# Stromsenke_Board.net
KiCad netlist of a schematic drawn in EAGLE
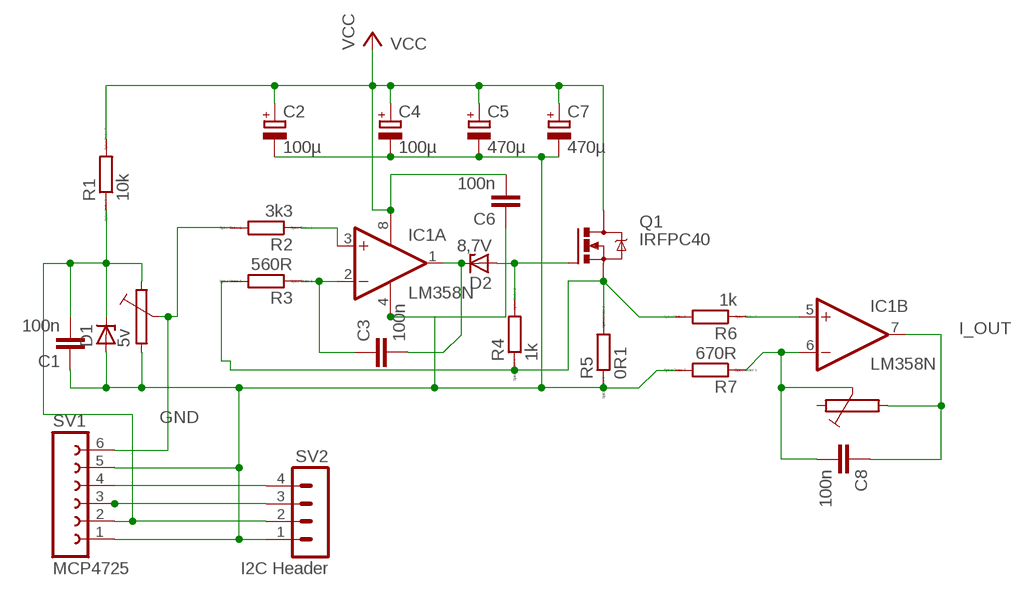
[diagram p0: schematic, sheet 1]

(export (version "E")
  (design (tool "Eeschema 10.0.6"))
  (components
    (comp (ref "C1")
      (value "100n")
      (footprint "eagle-import:C5B2.5")
      (libsource (lib "eagle-import") (part "C5/2.5"))
    )
    (comp (ref "C2")
      (value "100µ")
      (footprint "eagle-import:E3,5-8")
      (libsource (lib "eagle-import") (part "CPOL-EUE3.5-8"))
    )
    (comp (ref "C3")
      (value "100n")
      (footprint "eagle-import:C5B2.5")
      (libsource (lib "eagle-import") (part "C5/2.5"))
    )
    (comp (ref "C4")
      (value "100µ")
      (footprint "eagle-import:E3,5-8")
      (libsource (lib "eagle-import") (part "CPOL-EUE3.5-8"))
    )
    (comp (ref "C5")
      (value "470µ")
      (footprint "eagle-import:E3,5-10")
      (libsource (lib "eagle-import") (part "CPOL-EUE3.5-10"))
    )
    (comp (ref "C6")
      (value "100n")
      (footprint "eagle-import:C5B2.5")
      (libsource (lib "eagle-import") (part "C5/2.5"))
    )
    (comp (ref "C7")
      (value "470µ")
      (footprint "eagle-import:E3,5-10")
      (libsource (lib "eagle-import") (part "CPOL-EUE3.5-10"))
    )
    (comp (ref "C8")
      (value "100n")
      (footprint "eagle-import:C5B2.5")
      (libsource (lib "eagle-import") (part "C5/2.5"))
    )
    (comp (ref "D1")
      (value "5v")
      (footprint "eagle-import:C1702-15")
      (libsource (lib "eagle-import") (part "ZENER-DIODEC1702-15"))
    )
    (comp (ref "D2")
      (value "8,7V")
      (footprint "eagle-import:C1702-15")
      (libsource (lib "eagle-import") (part "ZENER-DIODEC1702-15"))
    )
    (comp (ref "IC1")
      (value "LM358N")
      (footprint "eagle-import:DIL08")
      (libsource (lib "eagle-import") (part "LM358N"))
    )
    (comp (ref "Q1")
      (value "IRFPC40")
      (footprint "eagle-import:TO247BV")
      (libsource (lib "eagle-import") (part "IRFPC40"))
    )
    (comp (ref "R1")
      (value "10k")
      (footprint "eagle-import:0207_10")
      (libsource (lib "eagle-import") (part "R0207/10"))
    )
    (comp (ref "R2")
      (value "3k3")
      (footprint "eagle-import:0207_10")
      (libsource (lib "eagle-import") (part "R0207/10"))
    )
    (comp (ref "R3")
      (value "560R")
      (footprint "eagle-import:0207_10")
      (libsource (lib "eagle-import") (part "R0207/10"))
    )
    (comp (ref "R4")
      (value "1k")
      (footprint "eagle-import:0207_10")
      (libsource (lib "eagle-import") (part "R0207/10"))
    )
    (comp (ref "R5")
      (value "0R1")
      (footprint "eagle-import:0207_10")
      (libsource (lib "eagle-import") (part "R0207/10"))
    )
    (comp (ref "R6")
      (value "1k")
      (footprint "eagle-import:0207_10")
      (libsource (lib "eagle-import") (part "R0207/10"))
    )
    (comp (ref "R7")
      (value "670R")
      (footprint "eagle-import:0207_10")
      (libsource (lib "eagle-import") (part "R0207/10"))
    )
    (comp (ref "SV1")
      (value "MCP4725")
      (footprint "eagle-import:FE06")
      (libsource (lib "eagle-import") (part "FE06-1"))
    )
    (comp (ref "SV2")
      (value "I2C Header")
      (footprint "eagle-import:MA04-1")
      (libsource (lib "eagle-import") (part "MA04-1"))
    )
  )
  (nets
    (net (code "1") (name "GND") (class "Default")
      (node (ref "C1") (pin "1") (pinfunction "1_1") (pintype "passive"))
      (node (ref "C2") (pin "-") (pinfunction "-_-") (pintype "passive"))
      (node (ref "C4") (pin "-") (pinfunction "-_-") (pintype "passive"))
      (node (ref "C5") (pin "-") (pinfunction "-_-") (pintype "passive"))
      (node (ref "C6") (pin "1") (pinfunction "1_1") (pintype "passive"))
      (node (ref "C7") (pin "-") (pinfunction "-_-") (pintype "passive"))
      (node (ref "D1") (pin "A") (pinfunction "A_A") (pintype "passive"))
      (node (ref "IC1") (pin "4") (pinfunction "V-_4") (pintype "power_in"))
      (node (ref "R5") (pin "1") (pinfunction "1_1") (pintype "passive"))
      (node (ref "R7") (pin "2") (pinfunction "2_2") (pintype "passive"))
      (node (ref "SV1") (pin "1") (pinfunction "1_1") (pintype "passive"))
      (node (ref "SV1") (pin "5") (pinfunction "5_5") (pintype "passive"))
      (node (ref "SV2") (pin "1") (pinfunction "1_1") (pintype "passive"))
    )
    (net (code "2") (name "I_OUT") (class "Default")
      (node (ref "C8") (pin "1") (pinfunction "1_1") (pintype "passive"))
      (node (ref "IC1") (pin "7") (pinfunction "OUT_7") (pintype "output"))
    )
    (net (code "3") (name "Net-(C1-Pad2)") (class "Default")
      (node (ref "C1") (pin "2") (pinfunction "2_2") (pintype "passive"))
      (node (ref "D1") (pin "C") (pinfunction "C_C") (pintype "passive"))
      (node (ref "R1") (pin "1") (pinfunction "1_1") (pintype "passive"))
      (node (ref "SV1") (pin "2") (pinfunction "2_2") (pintype "passive"))
      (node (ref "SV2") (pin "2") (pinfunction "2_2") (pintype "passive"))
    )
    (net (code "4") (name "Net-(D2-PadA)") (class "Default")
      (node (ref "D2") (pin "A") (pinfunction "A_A") (pintype "passive"))
      (node (ref "Q1") (pin "G") (pinfunction "G_G") (pintype "passive"))
      (node (ref "R4") (pin "2") (pinfunction "2_2") (pintype "passive"))
    )
    (net (code "5") (name "Net-(IC1A-+IN)") (class "Default")
      (node (ref "IC1") (pin "3") (pinfunction "+IN_3") (pintype "input"))
      (node (ref "R2") (pin "1") (pinfunction "1_1") (pintype "passive"))
    )
    (net (code "6") (name "Net-(IC1A--IN)") (class "Default")
      (node (ref "C3") (pin "1") (pinfunction "1_1") (pintype "passive"))
      (node (ref "IC1") (pin "2") (pinfunction "-IN_2") (pintype "input"))
      (node (ref "R3") (pin "1") (pinfunction "1_1") (pintype "passive"))
    )
    (net (code "7") (name "Net-(IC1A-OUT)") (class "Default")
      (node (ref "C3") (pin "2") (pinfunction "2_2") (pintype "passive"))
      (node (ref "D2") (pin "C") (pinfunction "C_C") (pintype "passive"))
      (node (ref "IC1") (pin "1") (pinfunction "OUT_1") (pintype "output"))
    )
    (net (code "8") (name "Net-(IC1B-+IN)") (class "Default")
      (node (ref "IC1") (pin "5") (pinfunction "+IN_5") (pintype "input"))
      (node (ref "R6") (pin "1") (pinfunction "1_1") (pintype "passive"))
    )
    (net (code "9") (name "Net-(IC1B--IN)") (class "Default")
      (node (ref "C8") (pin "2") (pinfunction "2_2") (pintype "passive"))
      (node (ref "IC1") (pin "6") (pinfunction "-IN_6") (pintype "input"))
      (node (ref "R7") (pin "1") (pinfunction "1_1") (pintype "passive"))
    )
    (net (code "10") (name "Net-(Q1-PadS)") (class "Default")
      (node (ref "Q1") (pin "S") (pinfunction "S_S") (pintype "passive"))
      (node (ref "R3") (pin "2") (pinfunction "2_2") (pintype "passive"))
      (node (ref "R4") (pin "1") (pinfunction "1_1") (pintype "passive"))
      (node (ref "R5") (pin "2") (pinfunction "2_2") (pintype "passive"))
      (node (ref "R6") (pin "2") (pinfunction "2_2") (pintype "passive"))
    )
    (net (code "11") (name "Net-(R2-Pad2)") (class "Default")
      (node (ref "R2") (pin "2") (pinfunction "2_2") (pintype "passive"))
      (node (ref "SV1") (pin "6") (pinfunction "6_6") (pintype "passive"))
    )
    (net (code "12") (name "Net-(SV1-Pad3)") (class "Default")
      (node (ref "SV1") (pin "3") (pinfunction "3_3") (pintype "passive"))
      (node (ref "SV2") (pin "3") (pinfunction "3_3") (pintype "passive"))
    )
    (net (code "13") (name "Net-(SV1-Pad4)") (class "Default")
      (node (ref "SV1") (pin "4") (pinfunction "4_4") (pintype "passive"))
      (node (ref "SV2") (pin "4") (pinfunction "4_4") (pintype "passive"))
    )
    (net (code "14") (name "VCC") (class "Default")
      (node (ref "C2") (pin "+") (pinfunction "+_+") (pintype "passive"))
      (node (ref "C4") (pin "+") (pinfunction "+_+") (pintype "passive"))
      (node (ref "C5") (pin "+") (pinfunction "+_+") (pintype "passive"))
      (node (ref "C6") (pin "2") (pinfunction "2_2") (pintype "passive"))
      (node (ref "C7") (pin "+") (pinfunction "+_+") (pintype "passive"))
      (node (ref "IC1") (pin "8") (pinfunction "V+_8") (pintype "power_in"))
      (node (ref "Q1") (pin "D") (pinfunction "D_D") (pintype "passive"))
      (node (ref "R1") (pin "2") (pinfunction "2_2") (pintype "passive"))
    )
  )
)
